# lightplay2a.net
KiCad netlist of a schematic drawn in EAGLE
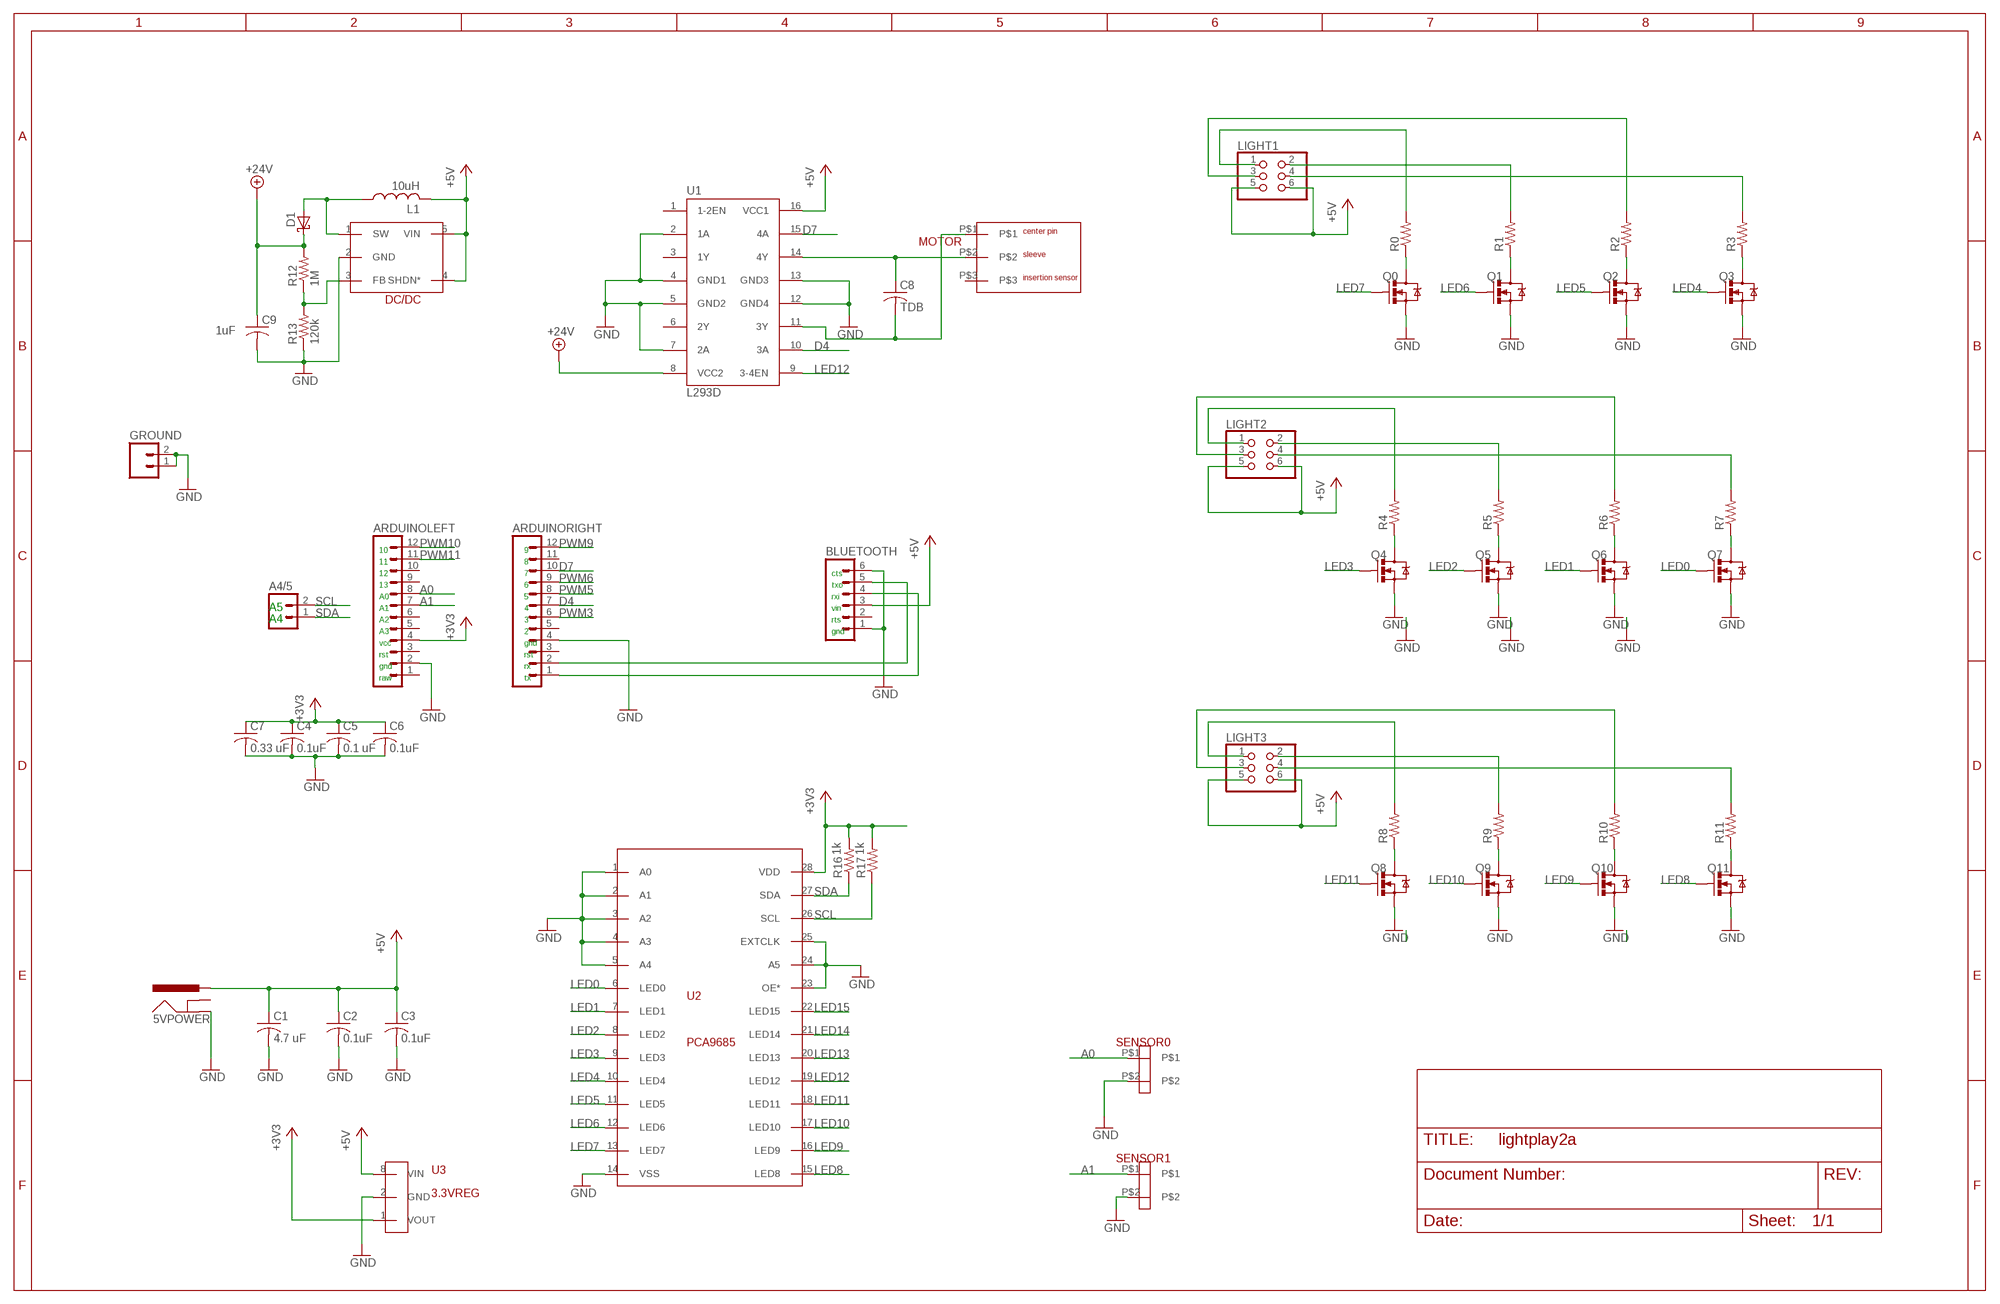
[diagram p0: schematic, sheet 1]

(export (version "E")
  (design (tool "Eeschema 10.0.6"))
  (components
    (comp (ref "5VPOWER")
      (value "POWER_JACKPTH")
      (footprint "eagle-import:POWER_JACK_PTH")
      (libsource (lib "eagle-import") (part "POWER_JACKPTH"))
    )
    (comp (ref "A4/5")
      (value "M02PTH")
      (footprint "eagle-import:1X02")
      (libsource (lib "eagle-import") (part "M02PTH"))
    )
    (comp (ref "ARDUINOLEFT")
      (value "M12PTH")
      (footprint "eagle-import:1X12")
      (libsource (lib "eagle-import") (part "M12PTH"))
    )
    (comp (ref "ARDUINORIGHT")
      (value "M12PTH")
      (footprint "eagle-import:1X12")
      (libsource (lib "eagle-import") (part "M12PTH"))
    )
    (comp (ref "BLUETOOTH")
      (value "M06SILK_FEMALE_PTH")
      (footprint "eagle-import:1X06")
      (libsource (lib "eagle-import") (part "M06SILK_FEMALE_PTH"))
    )
    (comp (ref "C1")
      (value "4.7 uF")
      (footprint "eagle-import:C1206")
      (libsource (lib "eagle-import") (part "C-USC1206"))
    )
    (comp (ref "C2")
      (value "0.1uF")
      (footprint "eagle-import:C0805")
      (libsource (lib "eagle-import") (part "C-USC0805"))
    )
    (comp (ref "C3")
      (value "0.1uF")
      (footprint "eagle-import:C0805")
      (libsource (lib "eagle-import") (part "C-USC0805"))
    )
    (comp (ref "C4")
      (value "0.1uF")
      (footprint "eagle-import:C0805")
      (libsource (lib "eagle-import") (part "C-USC0805"))
    )
    (comp (ref "C5")
      (value "0.1 uF")
      (footprint "eagle-import:C0805")
      (libsource (lib "eagle-import") (part "C-USC0805"))
    )
    (comp (ref "C6")
      (value "0.1uF")
      (footprint "eagle-import:C0805")
      (libsource (lib "eagle-import") (part "C-USC0805"))
    )
    (comp (ref "C7")
      (value "0.33 uF")
      (footprint "eagle-import:C1206")
      (libsource (lib "eagle-import") (part "C-USC1206"))
    )
    (comp (ref "C8")
      (value "TDB")
      (footprint "eagle-import:C0805")
      (libsource (lib "eagle-import") (part "C-USC0805"))
    )
    (comp (ref "C9")
      (value "1uF")
      (footprint "eagle-import:C1206")
      (libsource (lib "eagle-import") (part "C-USC1206"))
    )
    (comp (ref "D1")
      (value "B120_SHOTTKY_DIODE")
      (footprint "eagle-import:DO214AC")
      (libsource (lib "eagle-import") (part "B120_SHOTTKY_DIODE"))
    )
    (comp (ref "DC/DC")
      (value "LT1615")
      (footprint "eagle-import:SOT23-5")
      (libsource (lib "eagle-import") (part "LT1615"))
    )
    (comp (ref "GROUND")
      (value "M02PTH")
      (footprint "eagle-import:1X02")
      (libsource (lib "eagle-import") (part "M02PTH"))
    )
    (comp (ref "L1")
      (value "10uH")
      (footprint "eagle-import:INDUCTOR_WURTH")
      (libsource (lib "eagle-import") (part "INDUCTOR_WURTH"))
    )
    (comp (ref "LIGHT1")
      (value "PINHD-2X3")
      (footprint "eagle-import:2X03")
      (libsource (lib "eagle-import") (part "PINHD-2X3"))
    )
    (comp (ref "LIGHT2")
      (value "PINHD-2X3")
      (footprint "eagle-import:2X03")
      (libsource (lib "eagle-import") (part "PINHD-2X3"))
    )
    (comp (ref "LIGHT3")
      (value "PINHD-2X3")
      (footprint "eagle-import:2X03")
      (libsource (lib "eagle-import") (part "PINHD-2X3"))
    )
    (comp (ref "MOTOR")
      (value "PJ-075DH-SMT-TR")
      (footprint "eagle-import:PJ-075DH-SMT-TR")
      (libsource (lib "eagle-import") (part "PJ-075DH-SMT-TR"))
    )
    (comp (ref "Q0")
      (value "MOSFET-NCHANNELAO3404A")
      (footprint "eagle-import:SOT23-3")
      (libsource (lib "eagle-import") (part "MOSFET-NCHANNELAO3404A"))
    )
    (comp (ref "Q1")
      (value "MOSFET-NCHANNELAO3404A")
      (footprint "eagle-import:SOT23-3")
      (libsource (lib "eagle-import") (part "MOSFET-NCHANNELAO3404A"))
    )
    (comp (ref "Q2")
      (value "MOSFET-NCHANNELAO3404A")
      (footprint "eagle-import:SOT23-3")
      (libsource (lib "eagle-import") (part "MOSFET-NCHANNELAO3404A"))
    )
    (comp (ref "Q3")
      (value "MOSFET-NCHANNELAO3404A")
      (footprint "eagle-import:SOT23-3")
      (libsource (lib "eagle-import") (part "MOSFET-NCHANNELAO3404A"))
    )
    (comp (ref "Q4")
      (value "MOSFET-NCHANNELAO3404A")
      (footprint "eagle-import:SOT23-3")
      (libsource (lib "eagle-import") (part "MOSFET-NCHANNELAO3404A"))
    )
    (comp (ref "Q5")
      (value "MOSFET-NCHANNELAO3404A")
      (footprint "eagle-import:SOT23-3")
      (libsource (lib "eagle-import") (part "MOSFET-NCHANNELAO3404A"))
    )
    (comp (ref "Q6")
      (value "MOSFET-NCHANNELAO3404A")
      (footprint "eagle-import:SOT23-3")
      (libsource (lib "eagle-import") (part "MOSFET-NCHANNELAO3404A"))
    )
    (comp (ref "Q7")
      (value "MOSFET-NCHANNELAO3404A")
      (footprint "eagle-import:SOT23-3")
      (libsource (lib "eagle-import") (part "MOSFET-NCHANNELAO3404A"))
    )
    (comp (ref "Q8")
      (value "MOSFET-NCHANNELAO3404A")
      (footprint "eagle-import:SOT23-3")
      (libsource (lib "eagle-import") (part "MOSFET-NCHANNELAO3404A"))
    )
    (comp (ref "Q9")
      (value "MOSFET-NCHANNELAO3404A")
      (footprint "eagle-import:SOT23-3")
      (libsource (lib "eagle-import") (part "MOSFET-NCHANNELAO3404A"))
    )
    (comp (ref "Q10")
      (value "MOSFET-NCHANNELAO3404A")
      (footprint "eagle-import:SOT23-3")
      (libsource (lib "eagle-import") (part "MOSFET-NCHANNELAO3404A"))
    )
    (comp (ref "Q11")
      (value "MOSFET-NCHANNELAO3404A")
      (footprint "eagle-import:SOT23-3")
      (libsource (lib "eagle-import") (part "MOSFET-NCHANNELAO3404A"))
    )
    (comp (ref "R0")
      (value "R-US_0617/17")
      (footprint "eagle-import:0617_17")
      (libsource (lib "eagle-import") (part "robbie_R-US_0617/17"))
    )
    (comp (ref "R1")
      (value "R-US_0617/17")
      (footprint "eagle-import:0617_17")
      (libsource (lib "eagle-import") (part "robbie_R-US_0617/17"))
    )
    (comp (ref "R2")
      (value "R-US_0617/17")
      (footprint "eagle-import:0617_17")
      (libsource (lib "eagle-import") (part "robbie_R-US_0617/17"))
    )
    (comp (ref "R3")
      (value "R-US_0617/17")
      (footprint "eagle-import:0617_17")
      (libsource (lib "eagle-import") (part "robbie_R-US_0617/17"))
    )
    (comp (ref "R4")
      (value "R-US_0617/17")
      (footprint "eagle-import:0617_17")
      (libsource (lib "eagle-import") (part "robbie_R-US_0617/17"))
    )
    (comp (ref "R5")
      (value "R-US_0617/17")
      (footprint "eagle-import:0617_17")
      (libsource (lib "eagle-import") (part "robbie_R-US_0617/17"))
    )
    (comp (ref "R6")
      (value "R-US_0617/17")
      (footprint "eagle-import:0617_17")
      (libsource (lib "eagle-import") (part "robbie_R-US_0617/17"))
    )
    (comp (ref "R7")
      (value "R-US_0617/17")
      (footprint "eagle-import:0617_17")
      (libsource (lib "eagle-import") (part "robbie_R-US_0617/17"))
    )
    (comp (ref "R8")
      (value "R-US_0617/17")
      (footprint "eagle-import:0617_17")
      (libsource (lib "eagle-import") (part "robbie_R-US_0617/17"))
    )
    (comp (ref "R9")
      (value "R-US_0617/17")
      (footprint "eagle-import:0617_17")
      (libsource (lib "eagle-import") (part "robbie_R-US_0617/17"))
    )
    (comp (ref "R10")
      (value "R-US_0617/17")
      (footprint "eagle-import:0617_17")
      (libsource (lib "eagle-import") (part "robbie_R-US_0617/17"))
    )
    (comp (ref "R11")
      (value "R-US_0617/17")
      (footprint "eagle-import:0617_17")
      (libsource (lib "eagle-import") (part "robbie_R-US_0617/17"))
    )
    (comp (ref "R12")
      (value "1M")
      (footprint "eagle-import:R0805")
      (libsource (lib "eagle-import") (part "R-US_R0805"))
    )
    (comp (ref "R13")
      (value "120k")
      (footprint "eagle-import:R0805")
      (libsource (lib "eagle-import") (part "R-US_R0805"))
    )
    (comp (ref "R16")
      (value "1k")
      (footprint "eagle-import:R0805")
      (libsource (lib "eagle-import") (part "R-US_R0805"))
    )
    (comp (ref "R17")
      (value "1k")
      (footprint "eagle-import:R0805")
      (libsource (lib "eagle-import") (part "R-US_R0805"))
    )
    (comp (ref "SENSOR0")
      (value "3.5MM_2PIN_SCREWTERMINAL_SPARKFUN")
      (footprint "eagle-import:1X02_3.5_SCREWTERM")
      (libsource (lib "eagle-import") (part "3.5MM_2PIN_SCREWTERMINAL_SPARKFUN"))
    )
    (comp (ref "SENSOR1")
      (value "3.5MM_2PIN_SCREWTERMINAL_SPARKFUN")
      (footprint "eagle-import:1X02_3.5_SCREWTERM")
      (libsource (lib "eagle-import") (part "3.5MM_2PIN_SCREWTERMINAL_SPARKFUN"))
    )
    (comp (ref "U1")
      (value "L293D")
      (footprint "eagle-import:DIL16")
      (libsource (lib "eagle-import") (part "L293D"))
    )
    (comp (ref "U2")
      (value "PCA9685")
      (footprint "eagle-import:TSSOP28")
      (libsource (lib "eagle-import") (part "PCA9685"))
    )
    (comp (ref "U3")
      (value "3.3VREG")
      (footprint "eagle-import:SO08")
      (libsource (lib "eagle-import") (part "STM3.3VREG"))
    )
  )
  (nets
    (net (code "1") (name "+3V3") (class "Default")
      (node (ref "ARDUINOLEFT") (pin "4") (pinfunction "4_4") (pintype "passive"))
      (node (ref "C4") (pin "1") (pinfunction "1_1") (pintype "passive"))
      (node (ref "C5") (pin "1") (pinfunction "1_1") (pintype "passive"))
      (node (ref "C6") (pin "1") (pinfunction "1_1") (pintype "passive"))
      (node (ref "C7") (pin "1") (pinfunction "1_1") (pintype "passive"))
      (node (ref "R16") (pin "2") (pinfunction "2_2") (pintype "passive"))
      (node (ref "R17") (pin "2") (pinfunction "2_2") (pintype "passive"))
      (node (ref "U2") (pin "28") (pinfunction "VDD_28") (pintype "bidirectional"))
      (node (ref "U3") (pin "1") (pinfunction "VOUT_1") (pintype "bidirectional"))
    )
    (net (code "2") (name "+5V") (class "Default")
      (node (ref "5VPOWER") (pin "PWR") (pinfunction "PWR_PWR") (pintype "bidirectional"))
      (node (ref "BLUETOOTH") (pin "3") (pinfunction "3_3") (pintype "passive"))
      (node (ref "C1") (pin "1") (pinfunction "1_1") (pintype "passive"))
      (node (ref "C2") (pin "1") (pinfunction "1_1") (pintype "passive"))
      (node (ref "C3") (pin "1") (pinfunction "1_1") (pintype "passive"))
      (node (ref "DC/DC") (pin "4") (pinfunction "SHDN*_4") (pintype "bidirectional"))
      (node (ref "DC/DC") (pin "5") (pinfunction "VIN_5") (pintype "bidirectional"))
      (node (ref "L1") (pin "P$2") (pinfunction "2_P$2") (pintype "passive"))
      (node (ref "LIGHT1") (pin "5") (pinfunction "5_5") (pintype "passive"))
      (node (ref "LIGHT1") (pin "6") (pinfunction "6_6") (pintype "passive"))
      (node (ref "LIGHT2") (pin "5") (pinfunction "5_5") (pintype "passive"))
      (node (ref "LIGHT2") (pin "6") (pinfunction "6_6") (pintype "passive"))
      (node (ref "LIGHT3") (pin "5") (pinfunction "5_5") (pintype "passive"))
      (node (ref "LIGHT3") (pin "6") (pinfunction "6_6") (pintype "passive"))
      (node (ref "U1") (pin "16") (pinfunction "VCC1_16") (pintype "power_in"))
      (node (ref "U3") (pin "8") (pinfunction "VIN_8") (pintype "bidirectional"))
    )
    (net (code "3") (name "+24V") (class "Default")
      (node (ref "C9") (pin "1") (pinfunction "1_1") (pintype "passive"))
      (node (ref "D1") (pin "C") (pinfunction "C_C") (pintype "passive"))
      (node (ref "R12") (pin "2") (pinfunction "2_2") (pintype "passive"))
      (node (ref "U1") (pin "8") (pinfunction "VCC2_8") (pintype "power_in"))
    )
    (net (code "4") (name "/A0") (class "Default")
      (node (ref "ARDUINOLEFT") (pin "8") (pinfunction "8_8") (pintype "passive"))
      (node (ref "SENSOR0") (pin "P$1") (pinfunction "P$1_P$1") (pintype "bidirectional"))
    )
    (net (code "5") (name "/A1") (class "Default")
      (node (ref "ARDUINOLEFT") (pin "7") (pinfunction "7_7") (pintype "passive"))
      (node (ref "SENSOR1") (pin "P$1") (pinfunction "P$1_P$1") (pintype "bidirectional"))
    )
    (net (code "6") (name "/D4") (class "Default")
      (node (ref "ARDUINORIGHT") (pin "7") (pinfunction "7_7") (pintype "passive"))
      (node (ref "U1") (pin "10") (pinfunction "3A_10") (pintype "input"))
    )
    (net (code "7") (name "/D7") (class "Default")
      (node (ref "ARDUINORIGHT") (pin "10") (pinfunction "10_10") (pintype "passive"))
      (node (ref "U1") (pin "15") (pinfunction "4A_15") (pintype "input"))
    )
    (net (code "8") (name "/LED0") (class "Default")
      (node (ref "Q7") (pin "1") (pinfunction "G_1") (pintype "passive"))
      (node (ref "U2") (pin "6") (pinfunction "LED0_6") (pintype "bidirectional"))
    )
    (net (code "9") (name "/LED1") (class "Default")
      (node (ref "Q6") (pin "1") (pinfunction "G_1") (pintype "passive"))
      (node (ref "U2") (pin "7") (pinfunction "LED1_7") (pintype "bidirectional"))
    )
    (net (code "10") (name "/LED2") (class "Default")
      (node (ref "Q5") (pin "1") (pinfunction "G_1") (pintype "passive"))
      (node (ref "U2") (pin "8") (pinfunction "LED2_8") (pintype "bidirectional"))
    )
    (net (code "11") (name "/LED3") (class "Default")
      (node (ref "Q4") (pin "1") (pinfunction "G_1") (pintype "passive"))
      (node (ref "U2") (pin "9") (pinfunction "LED3_9") (pintype "bidirectional"))
    )
    (net (code "12") (name "/LED4") (class "Default")
      (node (ref "Q3") (pin "1") (pinfunction "G_1") (pintype "passive"))
      (node (ref "U2") (pin "10") (pinfunction "LED4_10") (pintype "bidirectional"))
    )
    (net (code "13") (name "/LED5") (class "Default")
      (node (ref "Q2") (pin "1") (pinfunction "G_1") (pintype "passive"))
      (node (ref "U2") (pin "11") (pinfunction "LED5_11") (pintype "bidirectional"))
    )
    (net (code "14") (name "/LED6") (class "Default")
      (node (ref "Q1") (pin "1") (pinfunction "G_1") (pintype "passive"))
      (node (ref "U2") (pin "12") (pinfunction "LED6_12") (pintype "bidirectional"))
    )
    (net (code "15") (name "/LED7") (class "Default")
      (node (ref "Q0") (pin "1") (pinfunction "G_1") (pintype "passive"))
      (node (ref "U2") (pin "13") (pinfunction "LED7_13") (pintype "bidirectional"))
    )
    (net (code "16") (name "/LED8") (class "Default")
      (node (ref "Q11") (pin "1") (pinfunction "G_1") (pintype "passive"))
      (node (ref "U2") (pin "15") (pinfunction "LED8_15") (pintype "bidirectional"))
    )
    (net (code "17") (name "/LED9") (class "Default")
      (node (ref "Q10") (pin "1") (pinfunction "G_1") (pintype "passive"))
      (node (ref "U2") (pin "16") (pinfunction "LED9_16") (pintype "bidirectional"))
    )
    (net (code "18") (name "/LED10") (class "Default")
      (node (ref "Q9") (pin "1") (pinfunction "G_1") (pintype "passive"))
      (node (ref "U2") (pin "17") (pinfunction "LED10_17") (pintype "bidirectional"))
    )
    (net (code "19") (name "/LED11") (class "Default")
      (node (ref "Q8") (pin "1") (pinfunction "G_1") (pintype "passive"))
      (node (ref "U2") (pin "18") (pinfunction "LED11_18") (pintype "bidirectional"))
    )
    (net (code "20") (name "/LED12") (class "Default")
      (node (ref "U1") (pin "9") (pinfunction "3-4EN_9") (pintype "input"))
      (node (ref "U2") (pin "19") (pinfunction "LED12_19") (pintype "bidirectional"))
    )
    (net (code "21") (name "/LED13") (class "Default")
      (node (ref "U2") (pin "20") (pinfunction "LED13_20") (pintype "bidirectional"))
    )
    (net (code "22") (name "/LED14") (class "Default")
      (node (ref "U2") (pin "21") (pinfunction "LED14_21") (pintype "bidirectional"))
    )
    (net (code "23") (name "/LED15") (class "Default")
      (node (ref "U2") (pin "22") (pinfunction "LED15_22") (pintype "bidirectional"))
    )
    (net (code "24") (name "/PWM3") (class "Default")
      (node (ref "ARDUINORIGHT") (pin "6") (pinfunction "6_6") (pintype "passive"))
    )
    (net (code "25") (name "/PWM5") (class "Default")
      (node (ref "ARDUINORIGHT") (pin "8") (pinfunction "8_8") (pintype "passive"))
    )
    (net (code "26") (name "/PWM6") (class "Default")
      (node (ref "ARDUINORIGHT") (pin "9") (pinfunction "9_9") (pintype "passive"))
    )
    (net (code "27") (name "/PWM9") (class "Default")
      (node (ref "ARDUINORIGHT") (pin "12") (pinfunction "12_12") (pintype "passive"))
    )
    (net (code "28") (name "/PWM10") (class "Default")
      (node (ref "ARDUINOLEFT") (pin "12") (pinfunction "12_12") (pintype "passive"))
    )
    (net (code "29") (name "/PWM11") (class "Default")
      (node (ref "ARDUINOLEFT") (pin "11") (pinfunction "11_11") (pintype "passive"))
    )
    (net (code "30") (name "/SCL") (class "Default")
      (node (ref "A4/5") (pin "2") (pinfunction "2_2") (pintype "passive"))
      (node (ref "R17") (pin "1") (pinfunction "1_1") (pintype "passive"))
      (node (ref "U2") (pin "26") (pinfunction "SCL_26") (pintype "bidirectional"))
    )
    (net (code "31") (name "/SDA") (class "Default")
      (node (ref "A4/5") (pin "1") (pinfunction "1_1") (pintype "passive"))
      (node (ref "R16") (pin "1") (pinfunction "1_1") (pintype "passive"))
      (node (ref "U2") (pin "27") (pinfunction "SDA_27") (pintype "bidirectional"))
    )
    (net (code "32") (name "GND") (class "Default")
      (node (ref "5VPOWER") (pin "GND") (pinfunction "GND_GND") (pintype "bidirectional"))
      (node (ref "ARDUINOLEFT") (pin "2") (pinfunction "2_2") (pintype "passive"))
      (node (ref "ARDUINORIGHT") (pin "4") (pinfunction "4_4") (pintype "passive"))
      (node (ref "BLUETOOTH") (pin "1") (pinfunction "1_1") (pintype "passive"))
      (node (ref "BLUETOOTH") (pin "6") (pinfunction "6_6") (pintype "passive"))
      (node (ref "C1") (pin "2") (pinfunction "2_2") (pintype "passive"))
      (node (ref "C2") (pin "2") (pinfunction "2_2") (pintype "passive"))
      (node (ref "C3") (pin "2") (pinfunction "2_2") (pintype "passive"))
      (node (ref "C4") (pin "2") (pinfunction "2_2") (pintype "passive"))
      (node (ref "C5") (pin "2") (pinfunction "2_2") (pintype "passive"))
      (node (ref "C6") (pin "2") (pinfunction "2_2") (pintype "passive"))
      (node (ref "C7") (pin "2") (pinfunction "2_2") (pintype "passive"))
      (node (ref "C9") (pin "2") (pinfunction "2_2") (pintype "passive"))
      (node (ref "DC/DC") (pin "2") (pinfunction "GND_2") (pintype "bidirectional"))
      (node (ref "GROUND") (pin "1") (pinfunction "1_1") (pintype "passive"))
      (node (ref "GROUND") (pin "2") (pinfunction "2_2") (pintype "passive"))
      (node (ref "Q0") (pin "2") (pinfunction "S_2") (pintype "passive"))
      (node (ref "Q1") (pin "2") (pinfunction "S_2") (pintype "passive"))
      (node (ref "Q10") (pin "2") (pinfunction "S_2") (pintype "passive"))
      (node (ref "Q11") (pin "2") (pinfunction "S_2") (pintype "passive"))
      (node (ref "Q2") (pin "2") (pinfunction "S_2") (pintype "passive"))
      (node (ref "Q3") (pin "2") (pinfunction "S_2") (pintype "passive"))
      (node (ref "Q4") (pin "2") (pinfunction "S_2") (pintype "passive"))
      (node (ref "Q5") (pin "2") (pinfunction "S_2") (pintype "passive"))
      (node (ref "Q6") (pin "2") (pinfunction "S_2") (pintype "passive"))
      (node (ref "Q7") (pin "2") (pinfunction "S_2") (pintype "passive"))
      (node (ref "Q8") (pin "2") (pinfunction "S_2") (pintype "passive"))
      (node (ref "Q9") (pin "2") (pinfunction "S_2") (pintype "passive"))
      (node (ref "R13") (pin "1") (pinfunction "1_1") (pintype "passive"))
      (node (ref "SENSOR0") (pin "P$2") (pinfunction "P$2_P$2") (pintype "bidirectional"))
      (node (ref "SENSOR1") (pin "P$2") (pinfunction "P$2_P$2") (pintype "bidirectional"))
      (node (ref "U1") (pin "12") (pinfunction "GND4_12") (pintype "power_in"))
      (node (ref "U1") (pin "13") (pinfunction "GND3_13") (pintype "power_in"))
      (node (ref "U1") (pin "2") (pinfunction "1A_2") (pintype "input"))
      (node (ref "U1") (pin "4") (pinfunction "GND1_4") (pintype "power_in"))
      (node (ref "U1") (pin "5") (pinfunction "GND2_5") (pintype "power_in"))
      (node (ref "U1") (pin "7") (pinfunction "2A_7") (pintype "input"))
      (node (ref "U2") (pin "1") (pinfunction "A0_1") (pintype "bidirectional"))
      (node (ref "U2") (pin "14") (pinfunction "VSS_14") (pintype "bidirectional"))
      (node (ref "U2") (pin "2") (pinfunction "A1_2") (pintype "bidirectional"))
      (node (ref "U2") (pin "23") (pinfunction "OE*_23") (pintype "bidirectional"))
      (node (ref "U2") (pin "24") (pinfunction "A5_24") (pintype "bidirectional"))
      (node (ref "U2") (pin "25") (pinfunction "EXTCLK_25") (pintype "bidirectional"))
      (node (ref "U2") (pin "3") (pinfunction "A2_3") (pintype "bidirectional"))
      (node (ref "U2") (pin "4") (pinfunction "A3_4") (pintype "bidirectional"))
      (node (ref "U2") (pin "5") (pinfunction "A4_5") (pintype "bidirectional"))
      (node (ref "U3") (pin "2") (pinfunction "GND_2") (pintype "bidirectional"))
    )
    (net (code "33") (name "Net-(ARDUINORIGHT-Pad1)") (class "Default")
      (node (ref "ARDUINORIGHT") (pin "1") (pinfunction "1_1") (pintype "passive"))
      (node (ref "BLUETOOTH") (pin "4") (pinfunction "4_4") (pintype "passive"))
    )
    (net (code "34") (name "Net-(ARDUINORIGHT-Pad2)") (class "Default")
      (node (ref "ARDUINORIGHT") (pin "2") (pinfunction "2_2") (pintype "passive"))
      (node (ref "BLUETOOTH") (pin "5") (pinfunction "5_5") (pintype "passive"))
    )
    (net (code "35") (name "Net-(DC/DC-FB)") (class "Default")
      (node (ref "DC/DC") (pin "3") (pinfunction "FB_3") (pintype "bidirectional"))
      (node (ref "R12") (pin "1") (pinfunction "1_1") (pintype "passive"))
      (node (ref "R13") (pin "2") (pinfunction "2_2") (pintype "passive"))
    )
    (net (code "36") (name "Net-(DC/DC-SW)") (class "Default")
      (node (ref "D1") (pin "A") (pinfunction "A_A") (pintype "passive"))
      (node (ref "DC/DC") (pin "1") (pinfunction "SW_1") (pintype "bidirectional"))
      (node (ref "L1") (pin "P$1") (pinfunction "1_P$1") (pintype "passive"))
    )
    (net (code "37") (name "Net-(LIGHT1-Pad1)") (class "Default")
      (node (ref "LIGHT1") (pin "1") (pinfunction "1_1") (pintype "passive"))
      (node (ref "R0") (pin "2") (pinfunction "2_2") (pintype "passive"))
    )
    (net (code "38") (name "Net-(LIGHT1-Pad2)") (class "Default")
      (node (ref "LIGHT1") (pin "2") (pinfunction "2_2") (pintype "passive"))
      (node (ref "R1") (pin "2") (pinfunction "2_2") (pintype "passive"))
    )
    (net (code "39") (name "Net-(LIGHT1-Pad3)") (class "Default")
      (node (ref "LIGHT1") (pin "3") (pinfunction "3_3") (pintype "passive"))
      (node (ref "R2") (pin "2") (pinfunction "2_2") (pintype "passive"))
    )
    (net (code "40") (name "Net-(LIGHT1-Pad4)") (class "Default")
      (node (ref "LIGHT1") (pin "4") (pinfunction "4_4") (pintype "passive"))
      (node (ref "R3") (pin "2") (pinfunction "2_2") (pintype "passive"))
    )
    (net (code "41") (name "Net-(LIGHT2-Pad1)") (class "Default")
      (node (ref "LIGHT2") (pin "1") (pinfunction "1_1") (pintype "passive"))
      (node (ref "R4") (pin "2") (pinfunction "2_2") (pintype "passive"))
    )
    (net (code "42") (name "Net-(LIGHT2-Pad2)") (class "Default")
      (node (ref "LIGHT2") (pin "2") (pinfunction "2_2") (pintype "passive"))
      (node (ref "R5") (pin "2") (pinfunction "2_2") (pintype "passive"))
    )
    (net (code "43") (name "Net-(LIGHT2-Pad3)") (class "Default")
      (node (ref "LIGHT2") (pin "3") (pinfunction "3_3") (pintype "passive"))
      (node (ref "R6") (pin "2") (pinfunction "2_2") (pintype "passive"))
    )
    (net (code "44") (name "Net-(LIGHT2-Pad4)") (class "Default")
      (node (ref "LIGHT2") (pin "4") (pinfunction "4_4") (pintype "passive"))
      (node (ref "R7") (pin "2") (pinfunction "2_2") (pintype "passive"))
    )
    (net (code "45") (name "Net-(LIGHT3-Pad1)") (class "Default")
      (node (ref "LIGHT3") (pin "1") (pinfunction "1_1") (pintype "passive"))
      (node (ref "R8") (pin "2") (pinfunction "2_2") (pintype "passive"))
    )
    (net (code "46") (name "Net-(LIGHT3-Pad2)") (class "Default")
      (node (ref "LIGHT3") (pin "2") (pinfunction "2_2") (pintype "passive"))
      (node (ref "R9") (pin "2") (pinfunction "2_2") (pintype "passive"))
    )
    (net (code "47") (name "Net-(LIGHT3-Pad3)") (class "Default")
      (node (ref "LIGHT3") (pin "3") (pinfunction "3_3") (pintype "passive"))
      (node (ref "R10") (pin "2") (pinfunction "2_2") (pintype "passive"))
    )
    (net (code "48") (name "Net-(LIGHT3-Pad4)") (class "Default")
      (node (ref "LIGHT3") (pin "4") (pinfunction "4_4") (pintype "passive"))
      (node (ref "R11") (pin "2") (pinfunction "2_2") (pintype "passive"))
    )
    (net (code "49") (name "Net-(Q0-D)") (class "Default")
      (node (ref "Q0") (pin "3") (pinfunction "D_3") (pintype "passive"))
      (node (ref "R0") (pin "1") (pinfunction "1_1") (pintype "passive"))
    )
    (net (code "50") (name "Net-(Q1-D)") (class "Default")
      (node (ref "Q1") (pin "3") (pinfunction "D_3") (pintype "passive"))
      (node (ref "R1") (pin "1") (pinfunction "1_1") (pintype "passive"))
    )
    (net (code "51") (name "Net-(Q2-D)") (class "Default")
      (node (ref "Q2") (pin "3") (pinfunction "D_3") (pintype "passive"))
      (node (ref "R2") (pin "1") (pinfunction "1_1") (pintype "passive"))
    )
    (net (code "52") (name "Net-(Q3-D)") (class "Default")
      (node (ref "Q3") (pin "3") (pinfunction "D_3") (pintype "passive"))
      (node (ref "R3") (pin "1") (pinfunction "1_1") (pintype "passive"))
    )
    (net (code "53") (name "Net-(Q4-D)") (class "Default")
      (node (ref "Q4") (pin "3") (pinfunction "D_3") (pintype "passive"))
      (node (ref "R4") (pin "1") (pinfunction "1_1") (pintype "passive"))
    )
    (net (code "54") (name "Net-(Q5-D)") (class "Default")
      (node (ref "Q5") (pin "3") (pinfunction "D_3") (pintype "passive"))
      (node (ref "R5") (pin "1") (pinfunction "1_1") (pintype "passive"))
    )
    (net (code "55") (name "Net-(Q6-D)") (class "Default")
      (node (ref "Q6") (pin "3") (pinfunction "D_3") (pintype "passive"))
      (node (ref "R6") (pin "1") (pinfunction "1_1") (pintype "passive"))
    )
    (net (code "56") (name "Net-(Q7-D)") (class "Default")
      (node (ref "Q7") (pin "3") (pinfunction "D_3") (pintype "passive"))
      (node (ref "R7") (pin "1") (pinfunction "1_1") (pintype "passive"))
    )
    (net (code "57") (name "Net-(Q8-D)") (class "Default")
      (node (ref "Q8") (pin "3") (pinfunction "D_3") (pintype "passive"))
      (node (ref "R8") (pin "1") (pinfunction "1_1") (pintype "passive"))
    )
    (net (code "58") (name "Net-(Q9-D)") (class "Default")
      (node (ref "Q9") (pin "3") (pinfunction "D_3") (pintype "passive"))
      (node (ref "R9") (pin "1") (pinfunction "1_1") (pintype "passive"))
    )
    (net (code "59") (name "Net-(Q10-D)") (class "Default")
      (node (ref "Q10") (pin "3") (pinfunction "D_3") (pintype "passive"))
      (node (ref "R10") (pin "1") (pinfunction "1_1") (pintype "passive"))
    )
    (net (code "60") (name "Net-(Q11-D)") (class "Default")
      (node (ref "Q11") (pin "3") (pinfunction "D_3") (pintype "passive"))
      (node (ref "R11") (pin "1") (pinfunction "1_1") (pintype "passive"))
    )
    (net (code "61") (name "Net-(U1-3Y)") (class "Default")
      (node (ref "C8") (pin "2") (pinfunction "2_2") (pintype "passive"))
      (node (ref "MOTOR") (pin "P$1") (pinfunction "P$1_P$1") (pintype "bidirectional"))
      (node (ref "U1") (pin "11") (pinfunction "3Y_11") (pintype "output"))
    )
    (net (code "62") (name "Net-(U1-4Y)") (class "Default")
      (node (ref "C8") (pin "1") (pinfunction "1_1") (pintype "passive"))
      (node (ref "MOTOR") (pin "P$2") (pinfunction "P$2_P$2") (pintype "bidirectional"))
      (node (ref "U1") (pin "14") (pinfunction "4Y_14") (pintype "output"))
    )
    (net (code "63") (name "unconnected-(5VPOWER-PadGNDBREAK)") (class "Default")
      (node (ref "5VPOWER") (pin "GNDBREAK") (pinfunction "GNDBREAK_GNDBREAK") (pintype "bidirectional"))
    )
    (net (code "64") (name "unconnected-(ARDUINOLEFT-Pad1)") (class "Default")
      (node (ref "ARDUINOLEFT") (pin "1") (pinfunction "1_1") (pintype "passive"))
    )
    (net (code "65") (name "unconnected-(ARDUINOLEFT-Pad3)") (class "Default")
      (node (ref "ARDUINOLEFT") (pin "3") (pinfunction "3_3") (pintype "passive"))
    )
    (net (code "66") (name "unconnected-(ARDUINOLEFT-Pad5)") (class "Default")
      (node (ref "ARDUINOLEFT") (pin "5") (pinfunction "5_5") (pintype "passive"))
    )
    (net (code "67") (name "unconnected-(ARDUINOLEFT-Pad6)") (class "Default")
      (node (ref "ARDUINOLEFT") (pin "6") (pinfunction "6_6") (pintype "passive"))
    )
    (net (code "68") (name "unconnected-(ARDUINOLEFT-Pad9)") (class "Default")
      (node (ref "ARDUINOLEFT") (pin "9") (pinfunction "9_9") (pintype "passive"))
    )
    (net (code "69") (name "unconnected-(ARDUINOLEFT-Pad10)") (class "Default")
      (node (ref "ARDUINOLEFT") (pin "10") (pinfunction "10_10") (pintype "passive"))
    )
    (net (code "70") (name "unconnected-(ARDUINORIGHT-Pad3)") (class "Default")
      (node (ref "ARDUINORIGHT") (pin "3") (pinfunction "3_3") (pintype "passive"))
    )
    (net (code "71") (name "unconnected-(ARDUINORIGHT-Pad5)") (class "Default")
      (node (ref "ARDUINORIGHT") (pin "5") (pinfunction "5_5") (pintype "passive"))
    )
    (net (code "72") (name "unconnected-(ARDUINORIGHT-Pad11)") (class "Default")
      (node (ref "ARDUINORIGHT") (pin "11") (pinfunction "11_11") (pintype "passive"))
    )
    (net (code "73") (name "unconnected-(BLUETOOTH-Pad2)") (class "Default")
      (node (ref "BLUETOOTH") (pin "2") (pinfunction "2_2") (pintype "passive"))
    )
    (net (code "74") (name "unconnected-(MOTOR-PadP$3)") (class "Default")
      (node (ref "MOTOR") (pin "P$3") (pinfunction "P$3_P$3") (pintype "bidirectional"))
    )
    (net (code "75") (name "unconnected-(U1-1-2EN-Pad1)") (class "Default")
      (node (ref "U1") (pin "1") (pinfunction "1-2EN_1") (pintype "input"))
    )
    (net (code "76") (name "unconnected-(U1-1Y-Pad3)") (class "Default")
      (node (ref "U1") (pin "3") (pinfunction "1Y_3") (pintype "output"))
    )
    (net (code "77") (name "unconnected-(U1-2Y-Pad6)") (class "Default")
      (node (ref "U1") (pin "6") (pinfunction "2Y_6") (pintype "output"))
    )
  )
)
